# Battery_PSU.net
KiCad netlist of a schematic drawn in Altium Designer
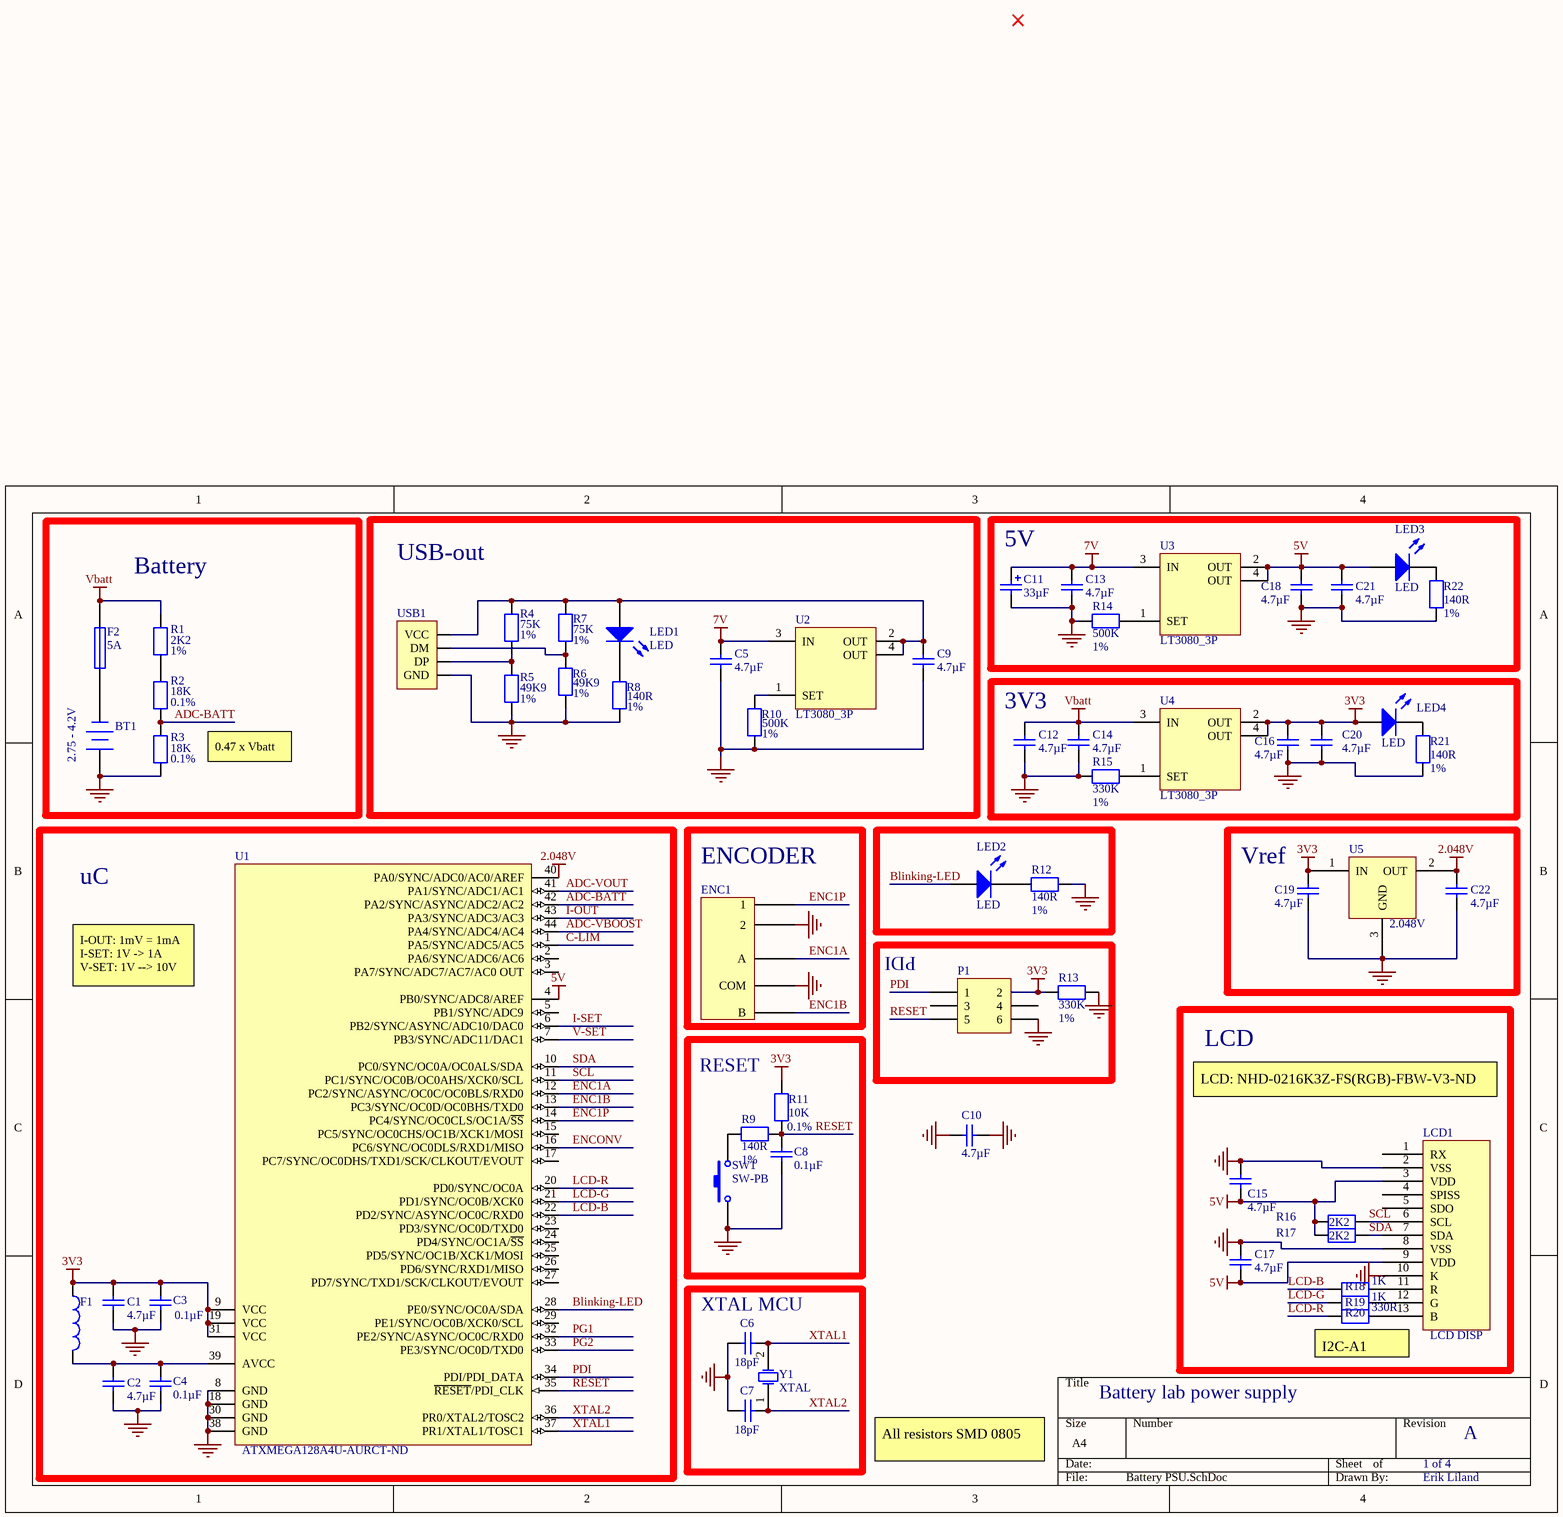
[diagram p0: Battery PSU.SchDoc]

(export (version "E")
  (design (tool "Eeschema 10.0.6"))
  (components
    (comp (ref "BT1")
      (value "2.75 - 4.2V")
      (footprint "BatteruPSU:Quad battery holder")
      (description "Multicell Battery")
      (fields
        (field (name "MANUFACTURER") "MPD (Memory Protection Devices)")
        (field (name "MANUFACTURER PART NUMBER") "BK-18650-PC8")
        (field (name "PUBLISHER") "Altium Limited")
      )
      (libsource (lib "BatteryPSU-parts") (part "Battery"))
    )
    (comp (ref "C1")
      (value "4.7µF")
      (footprint "BatteruPSU:0805_N_CAP")
      (description "Capacitor")
      (fields
        (field (name "MANUFACTURER") "Samsung Electro-Mechanics America, Inc")
        (field (name "MANUFACTURER PART NUMBER") "CL21B475KOFNFNE")
      )
      (libsource (lib "BatteryPSU-parts") (part "Cap"))
    )
    (comp (ref "C2")
      (value "4.7µF")
      (footprint "BatteruPSU:0805_N_CAP")
      (description "Capacitor")
      (fields
        (field (name "MANUFACTURER") "Samsung Electro-Mechanics America, Inc")
        (field (name "MANUFACTURER PART NUMBER") "CL21B475KOFNFNE")
      )
      (libsource (lib "BatteryPSU-parts") (part "Cap"))
    )
    (comp (ref "C3")
      (value "0.1µF")
      (footprint "BatteruPSU:0805_N_CAP")
      (description "Capacitor")
      (fields
        (field (name "MANUFACTURER") "Kemet")
        (field (name "MANUFACTURER PART NUMBER") "C0805C104K4RACTU")
      )
      (libsource (lib "BatteryPSU-parts") (part "Cap"))
    )
    (comp (ref "C4")
      (value "0.1µF")
      (footprint "BatteruPSU:0805_N_CAP")
      (description "Capacitor")
      (fields
        (field (name "MANUFACTURER") "Kemet")
        (field (name "MANUFACTURER PART NUMBER") "C0805C104K4RACTU")
      )
      (libsource (lib "BatteryPSU-parts") (part "Cap"))
    )
    (comp (ref "C5")
      (value "4.7µF")
      (footprint "BatteruPSU:0805_N_CAP")
      (description "Capacitor")
      (fields
        (field (name "MANUFACTURER") "Samsung Electro-Mechanics America, Inc")
        (field (name "MANUFACTURER PART NUMBER") "CL21B475KOFNFNE")
      )
      (libsource (lib "BatteryPSU-parts") (part "Cap"))
    )
    (comp (ref "C6")
      (value "18pF")
      (footprint "BatteruPSU:0805_N_CAP")
      (description "Capacitor")
      (fields
        (field (name "MANUFACTURER") "Samsung Electro-Mechanics America, Inc")
        (field (name "MANUFACTURER PART NUMBER") "CL21C180GBANNNC")
      )
      (libsource (lib "BatteryPSU-parts") (part "Cap"))
    )
    (comp (ref "C7")
      (value "18pF")
      (footprint "BatteruPSU:0805_N_CAP")
      (description "Capacitor")
      (fields
        (field (name "MANUFACTURER") "Samsung Electro-Mechanics America, Inc")
        (field (name "MANUFACTURER PART NUMBER") "CL21C180GBANNNC")
      )
      (libsource (lib "BatteryPSU-parts") (part "Cap"))
    )
    (comp (ref "C8")
      (value "0.1µF")
      (footprint "BatteruPSU:0805_N_CAP")
      (description "Capacitor")
      (fields
        (field (name "MANUFACTURER") "Kemet")
        (field (name "MANUFACTURER PART NUMBER") "C0805C104K4RACTU")
      )
      (libsource (lib "BatteryPSU-parts") (part "Cap"))
    )
    (comp (ref "C9")
      (value "4.7µF")
      (footprint "BatteruPSU:0805_N_CAP")
      (description "Capacitor")
      (fields
        (field (name "MANUFACTURER") "Samsung Electro-Mechanics America, Inc")
        (field (name "MANUFACTURER PART NUMBER") "CL21B475KOFNFNE")
      )
      (libsource (lib "BatteryPSU-parts") (part "Cap"))
    )
    (comp (ref "C10")
      (value "4.7µF")
      (footprint "BatteruPSU:0805_N_CAP")
      (description "Capacitor")
      (fields
        (field (name "MANUFACTURER") "Samsung Electro-Mechanics America, Inc")
        (field (name "MANUFACTURER PART NUMBER") "CL21B475KOFNFNE")
      )
      (libsource (lib "BatteryPSU-parts") (part "Cap"))
    )
    (comp (ref "C11")
      (value "33µF")
      (footprint "BatteruPSU:CAP SMD (F)")
      (description "Polarized Capacitor")
      (fields
        (field (name "MANUFACTURER") "Panasonic Electronic Components")
        (field (name "MANUFACTURER PART NUMBER") "EEH-ZA1E330R")
      )
      (libsource (lib "BatteryPSU-parts") (part "Cap Pol"))
    )
    (comp (ref "C12")
      (value "4.7µF")
      (footprint "BatteruPSU:0805_N_CAP")
      (description "Capacitor")
      (fields
        (field (name "MANUFACTURER") "Samsung Electro-Mechanics America, Inc")
        (field (name "MANUFACTURER PART NUMBER") "CL21B475KOFNFNE")
      )
      (libsource (lib "BatteryPSU-parts") (part "Cap"))
    )
    (comp (ref "C13")
      (value "4.7µF")
      (footprint "BatteruPSU:0805_N_CAP")
      (description "Capacitor")
      (fields
        (field (name "MANUFACTURER") "Samsung Electro-Mechanics America, Inc")
        (field (name "MANUFACTURER PART NUMBER") "CL21B475KOFNFNE")
      )
      (libsource (lib "BatteryPSU-parts") (part "Cap"))
    )
    (comp (ref "C14")
      (value "4.7µF")
      (footprint "BatteruPSU:0805_N_CAP")
      (description "Capacitor")
      (fields
        (field (name "MANUFACTURER") "Samsung Electro-Mechanics America, Inc")
        (field (name "MANUFACTURER PART NUMBER") "CL21B475KOFNFNE")
      )
      (libsource (lib "BatteryPSU-parts") (part "Cap"))
    )
    (comp (ref "C15")
      (value "4.7µF")
      (footprint "BatteruPSU:0805_N_CAP")
      (description "Capacitor")
      (fields
        (field (name "MANUFACTURER") "Samsung Electro-Mechanics America, Inc")
        (field (name "MANUFACTURER PART NUMBER") "CL21B475KOFNFNE")
      )
      (libsource (lib "BatteryPSU-parts") (part "Cap"))
    )
    (comp (ref "C16")
      (value "4.7µF")
      (footprint "BatteruPSU:0805_N_CAP")
      (description "Capacitor")
      (fields
        (field (name "MANUFACTURER") "Samsung Electro-Mechanics America, Inc")
        (field (name "MANUFACTURER PART NUMBER") "CL21B475KOFNFNE")
      )
      (libsource (lib "BatteryPSU-parts") (part "Cap"))
    )
    (comp (ref "C17")
      (value "4.7µF")
      (footprint "BatteruPSU:0805_N_CAP")
      (description "Capacitor")
      (fields
        (field (name "MANUFACTURER") "Samsung Electro-Mechanics America, Inc")
        (field (name "MANUFACTURER PART NUMBER") "CL21B475KOFNFNE")
      )
      (libsource (lib "BatteryPSU-parts") (part "Cap"))
    )
    (comp (ref "C18")
      (value "4.7µF")
      (footprint "BatteruPSU:0805_N_CAP")
      (description "Capacitor")
      (fields
        (field (name "MANUFACTURER") "Samsung Electro-Mechanics America, Inc")
        (field (name "MANUFACTURER PART NUMBER") "CL21B475KOFNFNE")
      )
      (libsource (lib "BatteryPSU-parts") (part "Cap"))
    )
    (comp (ref "C19")
      (value "4.7µF")
      (footprint "BatteruPSU:0805_N_CAP")
      (description "Capacitor")
      (fields
        (field (name "MANUFACTURER") "Samsung Electro-Mechanics America, Inc")
        (field (name "MANUFACTURER PART NUMBER") "CL21B475KOFNFNE")
      )
      (libsource (lib "BatteryPSU-parts") (part "Cap"))
    )
    (comp (ref "C20")
      (value "4.7µF")
      (footprint "BatteruPSU:0805_N_CAP")
      (description "Capacitor")
      (fields
        (field (name "MANUFACTURER") "Samsung Electro-Mechanics America, Inc")
        (field (name "MANUFACTURER PART NUMBER") "CL21B475KOFNFNE")
      )
      (libsource (lib "BatteryPSU-parts") (part "Cap"))
    )
    (comp (ref "C21")
      (value "4.7µF")
      (footprint "BatteruPSU:0805_N_CAP")
      (description "Capacitor")
      (fields
        (field (name "MANUFACTURER") "Samsung Electro-Mechanics America, Inc")
        (field (name "MANUFACTURER PART NUMBER") "CL21B475KOFNFNE")
      )
      (libsource (lib "BatteryPSU-parts") (part "Cap"))
    )
    (comp (ref "C22")
      (value "4.7µF")
      (footprint "BatteruPSU:0805_N_CAP")
      (description "Capacitor")
      (fields
        (field (name "MANUFACTURER") "Samsung Electro-Mechanics America, Inc")
        (field (name "MANUFACTURER PART NUMBER") "CL21B475KOFNFNE")
      )
      (libsource (lib "BatteryPSU-parts") (part "Cap"))
    )
    (comp (ref "ENC1")
      (value "RotEnc")
      (footprint "Bourns rotary encoder")
      (description "RotaryEncoder")
      (fields
        (field (name "MANUFACTURER") "Bourns Inc.")
        (field (name "MANUFACTURER PART NUMBER") "PEC09-2220F-S0012")
      )
      (libsource (lib "BatteryPSU-parts") (part "RotEnc"))
    )
    (comp (ref "F1")
      (value "200 Ohm @ 100MHz")
      (footprint "BatteruPSU:0805_N_FER")
      (description "Ferrite Bead")
      (fields
        (field (name "MANUFACTURER") "Laird-Signal Integrity Products")
        (field (name "MANUFACTURER PART NUMBER") "LI0805G201R-10")
      )
      (libsource (lib "BatteryPSU-parts") (part "Ferite"))
    )
    (comp (ref "F2")
      (value "5A")
      (footprint "BatteruPSU:1812_N_FUSE")
      (description "Resetable fuse, SMD")
      (fields
        (field (name "MANUFACTURER") "Bel Fuse Inc")
        (field (name "MANUFACTURER PART NUMBER") "0ZCG0260FF2C")
        (field (name "CURRENT - TRIP (IT)") "5A")
      )
      (libsource (lib "BatteryPSU-parts") (part "Fuse"))
    )
    (comp (ref "LCD1")
      (value "LCD DISP")
      (footprint "BatteruPSU:14P header")
      (description "2x16 CHAR DISP, RGB")
      (fields
        (field (name "MANUFACTURER") "Sullins Connector Solutions")
        (field (name "MANUFACTURER PART NUMBER") "SBH11-NBPC-D07-SM-BK")
      )
      (libsource (lib "BatteryPSU-parts") (part "LCD DISP"))
    )
    (comp (ref "LED1")
      (value "LED")
      (footprint "BatteruPSU:0805_N_LED")
      (description "Typical RED, GREEN, YELLOW, AMBER")
      (fields
        (field (name "MANUFACTURER") "OSRAM Opto Semiconductors Inc")
        (field (name "MANUFACTURER PART NUMBER") "LG R971-KN-1")
      )
      (libsource (lib "BatteryPSU-parts") (part "LED"))
    )
    (comp (ref "LED2")
      (value "LED")
      (footprint "BatteruPSU:0805_N_LED")
      (description "Typical RED, GREEN, YELLOW, AMBER")
      (fields
        (field (name "MANUFACTURER") "OSRAM Opto Semiconductors Inc")
        (field (name "MANUFACTURER PART NUMBER") "LG R971-KN-1")
      )
      (libsource (lib "BatteryPSU-parts") (part "LED"))
    )
    (comp (ref "LED3")
      (value "LED")
      (footprint "BatteruPSU:0805_N_LED")
      (description "Typical RED, GREEN, YELLOW, AMBER")
      (fields
        (field (name "MANUFACTURER") "OSRAM Opto Semiconductors Inc")
        (field (name "MANUFACTURER PART NUMBER") "LG R971-KN-1")
      )
      (libsource (lib "BatteryPSU-parts") (part "LED"))
    )
    (comp (ref "LED4")
      (value "LED")
      (footprint "BatteruPSU:0805_N_LED")
      (description "Typical RED, GREEN, YELLOW, AMBER")
      (fields
        (field (name "MANUFACTURER") "OSRAM Opto Semiconductors Inc")
        (field (name "MANUFACTURER PART NUMBER") "LG R971-KN-1")
      )
      (libsource (lib "BatteryPSU-parts") (part "LED"))
    )
    (comp (ref "P1")
      (value "Header 3X2")
      (footprint "BatteruPSU:HDR2X3 SMD")
      (description "Header, 3-Pin, Dual row")
      (fields (field (name "MANUFACTURER") "FCI") (field (name "MANUFACTURER PART NUMBER") "95278-101A06LF"))
      (libsource (lib "BatteryPSU-parts") (part "Header 3X2"))
    )
    (comp (ref "R1")
      (value "2K2")
      (footprint "BatteruPSU:0805_N_RES")
      (description "Resistor")
      (fields
        (field (name "TOLERANCE") "1%")
        (field (name "MANUFACTURER") "Samsung Electro-Mechanics America, Inc")
        (field (name "MANUFACTURER PART NUMBER") "RC2012F222CS")
      )
      (libsource (lib "BatteryPSU-parts") (part "Res"))
    )
    (comp (ref "R2")
      (value "18K")
      (footprint "BatteruPSU:0805_N_RES")
      (description "Resistor")
      (fields
        (field (name "TOLERANCE") "0.1%")
        (field (name "MANUFACTURER") "Panasonic Electronic Components")
        (field (name "MANUFACTURER PART NUMBER") "ERA-6AEB183V")
      )
      (libsource (lib "") (part "Res_1"))
    )
    (comp (ref "R3")
      (value "18K")
      (footprint "BatteruPSU:0805_N_RES")
      (description "Resistor")
      (fields
        (field (name "TOLERANCE") "0.1%")
        (field (name "MANUFACTURER") "Panasonic Electronic Components")
        (field (name "MANUFACTURER PART NUMBER") "ERA-6AEB183V")
      )
      (libsource (lib "") (part "Res_1"))
    )
    (comp (ref "R4")
      (value "75K")
      (footprint "BatteruPSU:0805_N_RES")
      (description "Resistor")
      (fields (field (name "TOLERANCE") "1%"))
      (libsource (lib "BatteryPSU-parts") (part "Res"))
    )
    (comp (ref "R5")
      (value "49K9")
      (footprint "BatteruPSU:0805_N_RES")
      (description "Resistor")
      (fields
        (field (name "TOLERANCE") "1%")
        (field (name "MANUFACTURER") "Samsung Electro-Mechanics America, Inc")
        (field (name "MANUFACTURER PART NUMBER") "RC2012F4992CS")
      )
      (libsource (lib "BatteryPSU-parts") (part "Res"))
    )
    (comp (ref "R6")
      (value "49K9")
      (footprint "BatteruPSU:0805_N_RES")
      (description "Resistor")
      (fields
        (field (name "TOLERANCE") "1%")
        (field (name "MANUFACTURER") "Samsung Electro-Mechanics America, Inc")
        (field (name "MANUFACTURER PART NUMBER") "RC2012F4992CS")
      )
      (libsource (lib "BatteryPSU-parts") (part "Res"))
    )
    (comp (ref "R7")
      (value "75K")
      (footprint "BatteruPSU:0805_N_RES")
      (description "Resistor")
      (fields (field (name "TOLERANCE") "1%"))
      (libsource (lib "BatteryPSU-parts") (part "Res"))
    )
    (comp (ref "R8")
      (value "140R")
      (footprint "BatteruPSU:0805_N_RES")
      (description "Resistor")
      (fields
        (field (name "TOLERANCE") "1%")
        (field (name "MANUFACTURER") "Samsung Electro-Mechanics America, Inc")
        (field (name "MANUFACTURER PART NUMBER") "RC2012F1400CS")
      )
      (libsource (lib "BatteryPSU-parts") (part "Res"))
    )
    (comp (ref "R9")
      (value "140R")
      (footprint "BatteruPSU:0805_N_RES")
      (description "Resistor")
      (fields
        (field (name "TOLERANCE") "1%")
        (field (name "MANUFACTURER") "Samsung Electro-Mechanics America, Inc")
        (field (name "MANUFACTURER PART NUMBER") "RC2012F1400CS")
      )
      (libsource (lib "") (part "Res_3"))
    )
    (comp (ref "R10")
      (value "500K")
      (footprint "BatteruPSU:0805_N_RES")
      (description "Resistor")
      (fields (field (name "TOLERANCE") "1%"))
      (libsource (lib "BatteryPSU-parts") (part "Res"))
    )
    (comp (ref "R11")
      (value "10K")
      (footprint "BatteruPSU:0805_N_RES")
      (description "Resistor")
      (fields
        (field (name "TOLERANCE") "0.1%")
        (field (name "MANUFACTURER") "TE Connectivity AMP Connectors")
        (field (name "MANUFACTURER PART NUMBER") "8-1614884-4")
      )
      (libsource (lib "") (part "Res_1"))
    )
    (comp (ref "R12")
      (value "140R")
      (footprint "BatteruPSU:0805_N_RES")
      (description "Resistor")
      (fields
        (field (name "TOLERANCE") "1%")
        (field (name "MANUFACTURER") "Samsung Electro-Mechanics America, Inc")
        (field (name "MANUFACTURER PART NUMBER") "RC2012F1400CS")
      )
      (libsource (lib "") (part "Res_2"))
    )
    (comp (ref "R13")
      (value "330K")
      (footprint "BatteruPSU:0805_N_RES")
      (description "Resistor")
      (fields
        (field (name "TOLERANCE") "1%")
        (field (name "MANUFACTURER") "Samsung Electro-Mechanics America, Inc")
        (field (name "MANUFACTURER PART NUMBER") "RC2012F331CS")
      )
      (libsource (lib "") (part "Res_2"))
    )
    (comp (ref "R14")
      (value "500K")
      (footprint "BatteruPSU:0805_N_RES")
      (description "Resistor")
      (fields (field (name "TOLERANCE") "1%"))
      (libsource (lib "") (part "Res_2"))
    )
    (comp (ref "R15")
      (value "330K")
      (footprint "BatteruPSU:0805_N_RES")
      (description "Resistor")
      (fields
        (field (name "TOLERANCE") "1%")
        (field (name "MANUFACTURER") "Samsung Electro-Mechanics America, Inc")
        (field (name "MANUFACTURER PART NUMBER") "RC2012F331CS")
      )
      (libsource (lib "") (part "Res_2"))
    )
    (comp (ref "R16")
      (value "2K2")
      (footprint "BatteruPSU:0805_N_RES")
      (description "Resistor")
      (fields
        (field (name "TOLERANCE") "1%")
        (field (name "MANUFACTURER") "Samsung Electro-Mechanics America, Inc")
      )
      (libsource (lib "") (part "Res_2"))
    )
    (comp (ref "R17")
      (value "2K2")
      (footprint "BatteruPSU:0805_N_RES")
      (description "Resistor")
      (fields
        (field (name "TOLERANCE") "1%")
        (field (name "MANUFACTURER") "Samsung Electro-Mechanics America, Inc")
      )
      (libsource (lib "") (part "Res_2"))
    )
    (comp (ref "R18")
      (value "1K")
      (footprint "BatteruPSU:0805_N_RES")
      (description "Resistor")
      (fields
        (field (name "TOLERANCE") "0.1%")
        (field (name "MANUFACTURER") "Panasonic Electronic Components")
      )
      (libsource (lib "") (part "Res_2"))
    )
    (comp (ref "R19")
      (value "1K")
      (footprint "BatteruPSU:0805_N_RES")
      (description "Resistor")
      (fields
        (field (name "TOLERANCE") "0.1%")
        (field (name "MANUFACTURER") "Panasonic Electronic Components")
      )
      (libsource (lib "") (part "Res_2"))
    )
    (comp (ref "R20")
      (value "330R")
      (footprint "BatteruPSU:0805_N_RES")
      (description "Resistor")
      (fields
        (field (name "TOLERANCE") "1%")
        (field (name "MANUFACTURER") "Samsung Electro-Mechanics America, Inc")
      )
      (libsource (lib "") (part "Res_2"))
    )
    (comp (ref "R21")
      (value "140R")
      (footprint "BatteruPSU:0805_N_RES")
      (description "Resistor")
      (fields
        (field (name "TOLERANCE") "1%")
        (field (name "MANUFACTURER") "Samsung Electro-Mechanics America, Inc")
        (field (name "MANUFACTURER PART NUMBER") "RC2012F1400CS")
      )
      (libsource (lib "") (part "Res_1"))
    )
    (comp (ref "R22")
      (value "140R")
      (footprint "BatteruPSU:0805_N_RES")
      (description "Resistor")
      (fields
        (field (name "TOLERANCE") "1%")
        (field (name "MANUFACTURER") "Samsung Electro-Mechanics America, Inc")
        (field (name "MANUFACTURER PART NUMBER") "RC2012F1400CS")
      )
      (libsource (lib "") (part "Res_1"))
    )
    (comp (ref "SW1")
      (value "SW-PB")
      (footprint "BatteruPSU:SW TACTILE")
      (description "Switch")
      (fields
        (field (name "MANUFACTURER") "C&K Components")
        (field (name "MANUFACTURER PART NUMBER") "PTS645SK50SMTR92 LFS")
        (field (name "PUBLISHER") "Altium Limited")
      )
      (libsource (lib "BatteryPSU-parts") (part "SW-PB"))
    )
    (comp (ref "U1")
      (value "ATxmega128A4-AU")
      (footprint "44A_N")
      (fields
        (field (name "SUPPLIER PART NUMBER 1") "ATXMEGA128A4U-AURCT-ND")
        (field (name "MANUFACTURER") "Atmel")
        (field (name "MANUFACTURER PART NUMBER") "ATXMEGA128A4U-AUR")
      )
      (libsource (lib "Altium Content Vault") (part "CMP-0094-00040-4"))
    )
    (comp (ref "U2")
      (value "LT3080_3P")
      (footprint "BatteruPSU:SOT223_N")
      (description "LT3080 LDO regulator")
      (fields
        (field (name "MANUFACTURER") "Linear Technology")
        (field (name "MANUFACTURER PART NUMBER") "LT3080EST#TRPBF")
      )
      (libsource (lib "BatteryPSU-parts") (part "LT3080_3P"))
    )
    (comp (ref "U3")
      (value "LT3080_3P")
      (footprint "BatteruPSU:SOT223_N")
      (description "LT3080 LDO regulator")
      (fields
        (field (name "MANUFACTURER") "Linear Technology")
        (field (name "MANUFACTURER PART NUMBER") "LT3080EST#TRPBF")
      )
      (libsource (lib "BatteryPSU-parts") (part "LT3080_3P"))
    )
    (comp (ref "U4")
      (value "LT3080_3P")
      (footprint "BatteruPSU:SOT223_N")
      (description "LT3080 LDO regulator")
      (fields
        (field (name "MANUFACTURER") "Linear Technology")
        (field (name "MANUFACTURER PART NUMBER") "LT3080EST#TRPBF")
      )
      (libsource (lib "BatteryPSU-parts") (part "LT3080_3P"))
    )
    (comp (ref "U5")
      (value "2.048V")
      (footprint "BatteruPSU:SOT-23_N")
      (description "Voltage reference")
      (fields
        (field (name "MANUFACTURER") "Intersil")
        (field (name "MANUFACTURER PART NUMBER") "ISL21010CFH320Z-TK")
      )
      (libsource (lib "BatteryPSU-parts") (part "ISL21010"))
    )
    (comp (ref "USB1")
      (value "USB_A_VERT")
      (footprint "BatteruPSU:USB A VERT")
      (description "USB A Vertikal")
      (fields
        (field (name "MANUFACTURER") "Assmann WSW Components")
        (field (name "MANUFACTURER PART NUMBER") "A-USB/2-A-E-R")
      )
      (libsource (lib "BatteryPSU-parts") (part "USB_A_VERT"))
    )
    (comp (ref "Y1")
      (value "XTAL")
      (footprint "BatteruPSU:XTAL SMD")
      (description "Crystal Oscillator")
      (fields
        (field (name "MANUFACTURER") "ECS Inc")
        (field (name "MANUFACTURER PART NUMBER") "ECS-80-18-20BQ-DS")
        (field (name "PUBLISHER") "Altium Limited")
      )
      (libsource (lib "BatteryPSU-parts") (part "XTAL"))
    )
  )
  (nets
    (net (code "1") (name "/ADC-BATT") (class "Default")
      (node (ref "R2") (pin "2") (pinfunction "2_2") (pintype "passive"))
      (node (ref "R3") (pin "1") (pinfunction "1_1") (pintype "passive"))
      (node (ref "U1") (pin "42") (pinfunction "PA2/SYNC/ASYNC/ADC2/AC2_42") (pintype "bidirectional"))
    )
    (net (code "2") (name "/ADC-VBOOST") (class "Default")
      (node (ref "U1") (pin "44") (pinfunction "PA4/SYNC/ADC4/AC4_44") (pintype "bidirectional"))
    )
    (net (code "3") (name "/ADC-VOUT") (class "Default")
      (node (ref "U1") (pin "41") (pinfunction "PA1/SYNC/ADC1/AC1_41") (pintype "bidirectional"))
    )
    (net (code "4") (name "/Blinking-LED") (class "Default")
      (node (ref "LED2") (pin "1") (pinfunction "A_1") (pintype "passive"))
      (node (ref "U1") (pin "28") (pinfunction "PE0/SYNC/OC0A/SDA_28") (pintype "bidirectional"))
    )
    (net (code "5") (name "/C-LIM") (class "Default")
      (node (ref "U1") (pin "1") (pinfunction "PA5/SYNC/ADC5/AC5_1") (pintype "bidirectional"))
    )
    (net (code "6") (name "/ENC1A") (class "Default")
      (node (ref "ENC1") (pin "A") (pinfunction "A_A") (pintype "passive"))
      (node (ref "U1") (pin "12") (pinfunction "PC2/SYNC/ASYNC/OC0C/OC0BLS/RXD0_12") (pintype "bidirectional"))
    )
    (net (code "7") (name "/ENC1B") (class "Default")
      (node (ref "ENC1") (pin "B") (pinfunction "B_B") (pintype "passive"))
      (node (ref "U1") (pin "13") (pinfunction "PC3/SYNC/OC0D/OC0BHS/TXD0_13") (pintype "bidirectional"))
    )
    (net (code "8") (name "/ENC1P") (class "Default")
      (node (ref "ENC1") (pin "D") (pinfunction "1_D") (pintype "passive"))
      (node (ref "U1") (pin "14") (pinfunction "PC4/SYNC/OC0CLS/OC1A/~{SS}_14") (pintype "bidirectional"))
    )
    (net (code "9") (name "/ENCONV") (class "Default")
      (node (ref "U1") (pin "16") (pinfunction "PC6/SYNC/OC0DLS/RXD1/MISO_16") (pintype "bidirectional"))
    )
    (net (code "10") (name "/I-OUT") (class "Default")
      (node (ref "U1") (pin "43") (pinfunction "PA3/SYNC/ADC3/AC3_43") (pintype "bidirectional"))
    )
    (net (code "11") (name "/I-SET") (class "Default")
      (node (ref "U1") (pin "6") (pinfunction "PB2/SYNC/ASYNC/ADC10/DAC0_6") (pintype "bidirectional"))
    )
    (net (code "12") (name "/LCD-B") (class "Default")
      (node (ref "R18") (pin "2") (pinfunction "2_2") (pintype "passive"))
      (node (ref "U1") (pin "22") (pinfunction "PD2/SYNC/ASYNC/OC0C/RXD0_22") (pintype "bidirectional"))
    )
    (net (code "13") (name "/LCD-G") (class "Default")
      (node (ref "R19") (pin "2") (pinfunction "2_2") (pintype "passive"))
      (node (ref "U1") (pin "21") (pinfunction "PD1/SYNC/OC0B/XCK0_21") (pintype "bidirectional"))
    )
    (net (code "14") (name "/LCD-R") (class "Default")
      (node (ref "R20") (pin "2") (pinfunction "2_2") (pintype "passive"))
      (node (ref "U1") (pin "20") (pinfunction "PD0/SYNC/OC0A_20") (pintype "bidirectional"))
    )
    (net (code "15") (name "/PDI") (class "Default")
      (node (ref "P1") (pin "1") (pinfunction "1_1") (pintype "passive"))
      (node (ref "U1") (pin "34") (pinfunction "PDI/PDI_DATA_34") (pintype "bidirectional"))
    )
    (net (code "16") (name "/PG1") (class "Default")
      (node (ref "U1") (pin "32") (pinfunction "PE2/SYNC/ASYNC/OC0C/RXD0_32") (pintype "bidirectional"))
    )
    (net (code "17") (name "/PG2") (class "Default")
      (node (ref "U1") (pin "33") (pinfunction "PE3/SYNC/OC0D/TXD0_33") (pintype "bidirectional"))
    )
    (net (code "18") (name "/RESET") (class "Default")
      (node (ref "C8") (pin "2") (pinfunction "2_2") (pintype "passive"))
      (node (ref "P1") (pin "5") (pinfunction "5_5") (pintype "passive"))
      (node (ref "R11") (pin "2") (pinfunction "2_2") (pintype "passive"))
      (node (ref "R9") (pin "2") (pinfunction "2_2") (pintype "passive"))
      (node (ref "U1") (pin "35") (pinfunction "~{RESET}/PDI_CLK_35") (pintype "input"))
    )
    (net (code "19") (name "/SCL") (class "Default")
      (node (ref "LCD1") (pin "6") (pinfunction "SCL_6") (pintype "passive"))
      (node (ref "R16") (pin "1") (pinfunction "1_1") (pintype "passive"))
      (node (ref "U1") (pin "11") (pinfunction "PC1/SYNC/OC0B/OC0AHS/XCK0/SCL_11") (pintype "bidirectional"))
    )
    (net (code "20") (name "/SDA") (class "Default")
      (node (ref "LCD1") (pin "7") (pinfunction "SDA_7") (pintype "passive"))
      (node (ref "R17") (pin "1") (pinfunction "1_1") (pintype "passive"))
      (node (ref "U1") (pin "10") (pinfunction "PC0/SYNC/OC0A/OC0ALS/SDA_10") (pintype "bidirectional"))
    )
    (net (code "21") (name "/V-SET") (class "Default")
      (node (ref "U1") (pin "7") (pinfunction "PB3/SYNC/ADC11/DAC1_7") (pintype "bidirectional"))
    )
    (net (code "22") (name "/XTAL1") (class "Default")
      (node (ref "C6") (pin "2") (pinfunction "2_2") (pintype "passive"))
      (node (ref "U1") (pin "37") (pinfunction "PR1/XTAL1/TOSC1_37") (pintype "bidirectional"))
      (node (ref "Y1") (pin "2") (pinfunction "OSC2_2") (pintype "passive"))
    )
    (net (code "23") (name "/XTAL2") (class "Default")
      (node (ref "C7") (pin "2") (pinfunction "2_2") (pintype "passive"))
      (node (ref "U1") (pin "36") (pinfunction "PR0/XTAL2/TOSC2_36") (pintype "bidirectional"))
      (node (ref "Y1") (pin "1") (pinfunction "OSC1_1") (pintype "passive"))
    )
    (net (code "24") (name "2.048V") (class "Default")
      (node (ref "C22") (pin "1") (pinfunction "1_1") (pintype "passive"))
      (node (ref "U1") (pin "40") (pinfunction "PA0/SYNC/ADC0/AC0/AREF_40") (pintype "passive"))
      (node (ref "U5") (pin "2") (pinfunction "OUT_2") (pintype "passive"))
    )
    (net (code "25") (name "3V3") (class "Default")
      (node (ref "C1") (pin "1") (pinfunction "1_1") (pintype "passive"))
      (node (ref "C16") (pin "1") (pinfunction "1_1") (pintype "passive"))
      (node (ref "C19") (pin "1") (pinfunction "1_1") (pintype "passive"))
      (node (ref "C20") (pin "1") (pinfunction "1_1") (pintype "passive"))
      (node (ref "C3") (pin "2") (pinfunction "2_2") (pintype "passive"))
      (node (ref "F1") (pin "1") (pinfunction "1_1") (pintype "passive"))
      (node (ref "LED4") (pin "1") (pinfunction "A_1") (pintype "passive"))
      (node (ref "P1") (pin "2") (pinfunction "2_2") (pintype "passive"))
      (node (ref "R11") (pin "1") (pinfunction "1_1") (pintype "passive"))
      (node (ref "R13") (pin "2") (pinfunction "2_2") (pintype "passive"))
      (node (ref "U1") (pin "19") (pinfunction "VCC_19") (pintype "power_in"))
      (node (ref "U1") (pin "31") (pinfunction "VCC_31") (pintype "power_in"))
      (node (ref "U1") (pin "9") (pinfunction "VCC_9") (pintype "power_in"))
      (node (ref "U4") (pin "2") (pinfunction "OUT_2") (pintype "passive"))
      (node (ref "U4") (pin "4") (pinfunction "OUT_4") (pintype "passive"))
      (node (ref "U5") (pin "1") (pinfunction "IN_1") (pintype "passive"))
    )
    (net (code "26") (name "5V") (class "Default")
      (node (ref "C15") (pin "2") (pinfunction "2_2") (pintype "passive"))
      (node (ref "C17") (pin "2") (pinfunction "2_2") (pintype "passive"))
      (node (ref "C18") (pin "1") (pinfunction "1_1") (pintype "passive"))
      (node (ref "C21") (pin "1") (pinfunction "1_1") (pintype "passive"))
      (node (ref "LCD1") (pin "3") (pinfunction "VDD_3") (pintype "passive"))
      (node (ref "LCD1") (pin "9") (pinfunction "VDD_9") (pintype "passive"))
      (node (ref "LED3") (pin "1") (pinfunction "A_1") (pintype "passive"))
      (node (ref "R16") (pin "2") (pinfunction "2_2") (pintype "passive"))
      (node (ref "R17") (pin "2") (pinfunction "2_2") (pintype "passive"))
      (node (ref "U1") (pin "4") (pinfunction "PB0/SYNC/ADC8/AREF_4") (pintype "passive"))
      (node (ref "U3") (pin "2") (pinfunction "OUT_2") (pintype "passive"))
      (node (ref "U3") (pin "4") (pinfunction "OUT_4") (pintype "passive"))
    )
    (net (code "27") (name "7V") (class "Default")
      (node (ref "C11") (pin "1") (pinfunction "1_1") (pintype "passive"))
      (node (ref "C13") (pin "1") (pinfunction "1_1") (pintype "passive"))
      (node (ref "C5") (pin "1") (pinfunction "1_1") (pintype "passive"))
      (node (ref "U2") (pin "3") (pinfunction "IN_3") (pintype "passive"))
      (node (ref "U3") (pin "3") (pinfunction "IN_3") (pintype "passive"))
    )
    (net (code "28") (name "GND") (class "Default")
      (node (ref "BT1") (pin "1") (pinfunction "+_1") (pintype "passive"))
      (node (ref "C1") (pin "2") (pinfunction "2_2") (pintype "passive"))
      (node (ref "C10") (pin "1") (pinfunction "1_1") (pintype "passive"))
      (node (ref "C10") (pin "2") (pinfunction "2_2") (pintype "passive"))
      (node (ref "C11") (pin "2") (pinfunction "2_2") (pintype "passive"))
      (node (ref "C12") (pin "2") (pinfunction "2_2") (pintype "passive"))
      (node (ref "C13") (pin "2") (pinfunction "2_2") (pintype "passive"))
      (node (ref "C14") (pin "2") (pinfunction "2_2") (pintype "passive"))
      (node (ref "C15") (pin "1") (pinfunction "1_1") (pintype "passive"))
      (node (ref "C16") (pin "2") (pinfunction "2_2") (pintype "passive"))
      (node (ref "C17") (pin "1") (pinfunction "1_1") (pintype "passive"))
      (node (ref "C18") (pin "2") (pinfunction "2_2") (pintype "passive"))
      (node (ref "C19") (pin "2") (pinfunction "2_2") (pintype "passive"))
      (node (ref "C2") (pin "2") (pinfunction "2_2") (pintype "passive"))
      (node (ref "C20") (pin "2") (pinfunction "2_2") (pintype "passive"))
      (node (ref "C21") (pin "2") (pinfunction "2_2") (pintype "passive"))
      (node (ref "C22") (pin "2") (pinfunction "2_2") (pintype "passive"))
      (node (ref "C3") (pin "1") (pinfunction "1_1") (pintype "passive"))
      (node (ref "C4") (pin "1") (pinfunction "1_1") (pintype "passive"))
      (node (ref "C5") (pin "2") (pinfunction "2_2") (pintype "passive"))
      (node (ref "C6") (pin "1") (pinfunction "1_1") (pintype "passive"))
      (node (ref "C7") (pin "1") (pinfunction "1_1") (pintype "passive"))
      (node (ref "C8") (pin "1") (pinfunction "1_1") (pintype "passive"))
      (node (ref "C9") (pin "2") (pinfunction "2_2") (pintype "passive"))
      (node (ref "ENC1") (pin "C") (pinfunction "COM_C") (pintype "passive"))
      (node (ref "ENC1") (pin "E") (pinfunction "2_E") (pintype "passive"))
      (node (ref "LCD1") (pin "10") (pinfunction "K_10") (pintype "passive"))
      (node (ref "LCD1") (pin "2") (pinfunction "VSS_2") (pintype "passive"))
      (node (ref "LCD1") (pin "8") (pinfunction "VSS_8") (pintype "passive"))
      (node (ref "P1") (pin "6") (pinfunction "6_6") (pintype "passive"))
      (node (ref "R10") (pin "1") (pinfunction "1_1") (pintype "passive"))
      (node (ref "R12") (pin "1") (pinfunction "1_1") (pintype "passive"))
      (node (ref "R13") (pin "1") (pinfunction "1_1") (pintype "passive"))
      (node (ref "R14") (pin "2") (pinfunction "2_2") (pintype "passive"))
      (node (ref "R15") (pin "2") (pinfunction "2_2") (pintype "passive"))
      (node (ref "R21") (pin "2") (pinfunction "2_2") (pintype "passive"))
      (node (ref "R22") (pin "2") (pinfunction "2_2") (pintype "passive"))
      (node (ref "R3") (pin "2") (pinfunction "2_2") (pintype "passive"))
      (node (ref "R5") (pin "1") (pinfunction "1_1") (pintype "passive"))
      (node (ref "R6") (pin "1") (pinfunction "1_1") (pintype "passive"))
      (node (ref "R8") (pin "1") (pinfunction "1_1") (pintype "passive"))
      (node (ref "SW1") (pin "1") (pinfunction "1_1") (pintype "passive"))
      (node (ref "U1") (pin "18") (pinfunction "GND_18") (pintype "power_in"))
      (node (ref "U1") (pin "30") (pinfunction "GND_30") (pintype "power_in"))
      (node (ref "U1") (pin "38") (pinfunction "GND_38") (pintype "power_in"))
      (node (ref "U1") (pin "8") (pinfunction "GND_8") (pintype "power_in"))
      (node (ref "U5") (pin "3") (pinfunction "GND_3") (pintype "passive"))
      (node (ref "USB1") (pin "4") (pinfunction "GND_4") (pintype "passive"))
    )
    (net (code "29") (name "Net-(BT1--)") (class "Default")
      (node (ref "BT1") (pin "2") (pinfunction "-_2") (pintype "passive"))
      (node (ref "F2") (pin "2") (pinfunction "2_2") (pintype "passive"))
    )
    (net (code "30") (name "Net-(LCD1-B)") (class "Default")
      (node (ref "LCD1") (pin "13") (pinfunction "B_13") (pintype "passive"))
      (node (ref "R20") (pin "1") (pinfunction "1_1") (pintype "passive"))
    )
    (net (code "31") (name "Net-(LCD1-G)") (class "Default")
      (node (ref "LCD1") (pin "12") (pinfunction "G_12") (pintype "passive"))
      (node (ref "R19") (pin "1") (pinfunction "1_1") (pintype "passive"))
    )
    (net (code "32") (name "Net-(LCD1-R)") (class "Default")
      (node (ref "LCD1") (pin "11") (pinfunction "R_11") (pintype "passive"))
      (node (ref "R18") (pin "1") (pinfunction "1_1") (pintype "passive"))
    )
    (net (code "33") (name "Net-(LED1-A)") (class "Default")
      (node (ref "C9") (pin "1") (pinfunction "1_1") (pintype "passive"))
      (node (ref "LED1") (pin "1") (pinfunction "A_1") (pintype "passive"))
      (node (ref "R4") (pin "2") (pinfunction "2_2") (pintype "passive"))
      (node (ref "R7") (pin "2") (pinfunction "2_2") (pintype "passive"))
      (node (ref "U2") (pin "2") (pinfunction "OUT_2") (pintype "passive"))
      (node (ref "U2") (pin "4") (pinfunction "OUT_4") (pintype "passive"))
      (node (ref "USB1") (pin "1") (pinfunction "VCC_1") (pintype "passive"))
    )
    (net (code "34") (name "Net-(LED1-K)") (class "Default")
      (node (ref "LED1") (pin "2") (pinfunction "K_2") (pintype "passive"))
      (node (ref "R8") (pin "2") (pinfunction "2_2") (pintype "passive"))
    )
    (net (code "35") (name "Net-(LED2-K)") (class "Default")
      (node (ref "LED2") (pin "2") (pinfunction "K_2") (pintype "passive"))
      (node (ref "R12") (pin "2") (pinfunction "2_2") (pintype "passive"))
    )
    (net (code "36") (name "Net-(LED3-K)") (class "Default")
      (node (ref "LED3") (pin "2") (pinfunction "K_2") (pintype "passive"))
      (node (ref "R22") (pin "1") (pinfunction "1_1") (pintype "passive"))
    )
    (net (code "37") (name "Net-(LED4-K)") (class "Default")
      (node (ref "LED4") (pin "2") (pinfunction "K_2") (pintype "passive"))
      (node (ref "R21") (pin "1") (pinfunction "1_1") (pintype "passive"))
    )
    (net (code "38") (name "Net-(R1-Pad1)") (class "Default")
      (node (ref "R1") (pin "1") (pinfunction "1_1") (pintype "passive"))
      (node (ref "R2") (pin "1") (pinfunction "1_1") (pintype "passive"))
    )
    (net (code "39") (name "Net-(R9-Pad1)") (class "Default")
      (node (ref "R9") (pin "1") (pinfunction "1_1") (pintype "passive"))
      (node (ref "SW1") (pin "2") (pinfunction "2_2") (pintype "passive"))
    )
    (net (code "40") (name "Net-(U1-AVCC)") (class "Default")
      (node (ref "C2") (pin "1") (pinfunction "1_1") (pintype "passive"))
      (node (ref "C4") (pin "2") (pinfunction "2_2") (pintype "passive"))
      (node (ref "F1") (pin "2") (pinfunction "2_2") (pintype "passive"))
      (node (ref "U1") (pin "39") (pinfunction "AVCC_39") (pintype "power_in"))
    )
    (net (code "41") (name "Net-(U2-SET)") (class "Default")
      (node (ref "R10") (pin "2") (pinfunction "2_2") (pintype "passive"))
      (node (ref "U2") (pin "1") (pinfunction "SET_1") (pintype "passive"))
    )
    (net (code "42") (name "Net-(U3-SET)") (class "Default")
      (node (ref "R14") (pin "1") (pinfunction "1_1") (pintype "passive"))
      (node (ref "U3") (pin "1") (pinfunction "SET_1") (pintype "passive"))
    )
    (net (code "43") (name "Net-(U4-SET)") (class "Default")
      (node (ref "R15") (pin "1") (pinfunction "1_1") (pintype "passive"))
      (node (ref "U4") (pin "1") (pinfunction "SET_1") (pintype "passive"))
    )
    (net (code "44") (name "Net-(USB1-DM)") (class "Default")
      (node (ref "R6") (pin "2") (pinfunction "2_2") (pintype "passive"))
      (node (ref "R7") (pin "1") (pinfunction "1_1") (pintype "passive"))
      (node (ref "USB1") (pin "2") (pinfunction "DM_2") (pintype "passive"))
    )
    (net (code "45") (name "Net-(USB1-DP)") (class "Default")
      (node (ref "R4") (pin "1") (pinfunction "1_1") (pintype "passive"))
      (node (ref "R5") (pin "2") (pinfunction "2_2") (pintype "passive"))
      (node (ref "USB1") (pin "3") (pinfunction "DP_3") (pintype "passive"))
    )
    (net (code "46") (name "Vbatt") (class "Default")
      (node (ref "C12") (pin "1") (pinfunction "1_1") (pintype "passive"))
      (node (ref "C14") (pin "1") (pinfunction "1_1") (pintype "passive"))
      (node (ref "F2") (pin "1") (pinfunction "1_1") (pintype "passive"))
      (node (ref "R1") (pin "2") (pinfunction "2_2") (pintype "passive"))
      (node (ref "U4") (pin "3") (pinfunction "IN_3") (pintype "passive"))
    )
    (net (code "47") (name "unconnected-(LCD1-RX-Pad1)") (class "Default")
      (node (ref "LCD1") (pin "1") (pinfunction "RX_1") (pintype "passive"))
    )
    (net (code "48") (name "unconnected-(LCD1-SDO-Pad5)") (class "Default")
      (node (ref "LCD1") (pin "5") (pinfunction "SDO_5") (pintype "passive"))
    )
    (net (code "49") (name "unconnected-(LCD1-SPISS-Pad4)") (class "Default")
      (node (ref "LCD1") (pin "4") (pinfunction "SPISS_4") (pintype "passive"))
    )
    (net (code "50") (name "unconnected-(P1-Pad3)") (class "Default")
      (node (ref "P1") (pin "3") (pinfunction "3_3") (pintype "passive"))
    )
    (net (code "51") (name "unconnected-(P1-Pad4)") (class "Default")
      (node (ref "P1") (pin "4") (pinfunction "4_4") (pintype "passive"))
    )
    (net (code "52") (name "unconnected-(U1-PA6{slash}SYNC{slash}ADC6{slash}AC6-Pad2)") (class "Default")
      (node (ref "U1") (pin "2") (pinfunction "PA6/SYNC/ADC6/AC6_2") (pintype "bidirectional"))
    )
    (net (code "53") (name "unconnected-(U1-PA7{slash}SYNC{slash}ADC7{slash}AC7{slash}AC0_OUT-Pad3)") (class "Default")
      (node (ref "U1") (pin "3") (pinfunction "PA7/SYNC/ADC7/AC7/AC0_OUT_3") (pintype "bidirectional"))
    )
    (net (code "54") (name "unconnected-(U1-PB1{slash}SYNC{slash}ADC9-Pad5)") (class "Default")
      (node (ref "U1") (pin "5") (pinfunction "PB1/SYNC/ADC9_5") (pintype "bidirectional"))
    )
    (net (code "55") (name "unconnected-(U1-PC5{slash}SYNC{slash}OC0CHS{slash}OC1B{slash}XCK1{slash}MOSI-Pad15)") (class "Default")
      (node (ref "U1") (pin "15") (pinfunction "PC5/SYNC/OC0CHS/OC1B/XCK1/MOSI_15") (pintype "bidirectional"))
    )
    (net (code "56") (name "unconnected-(U1-PC7{slash}SYNC{slash}OC0DHS{slash}TXD1{slash}SCK{slash}CLKOUT{slash}EVOUT-Pad17)") (class "Default")
      (node (ref "U1") (pin "17") (pinfunction "PC7/SYNC/OC0DHS/TXD1/SCK/CLKOUT/EVOUT_17") (pintype "bidirectional"))
    )
    (net (code "57") (name "unconnected-(U1-PD3{slash}SYNC{slash}OC0D{slash}TXD0-Pad23)") (class "Default")
      (node (ref "U1") (pin "23") (pinfunction "PD3/SYNC/OC0D/TXD0_23") (pintype "bidirectional"))
    )
    (net (code "58") (name "unconnected-(U1-PD4{slash}SYNC{slash}OC1A{slash}~{SS}-Pad24)") (class "Default")
      (node (ref "U1") (pin "24") (pinfunction "PD4/SYNC/OC1A/~{SS}_24") (pintype "bidirectional"))
    )
    (net (code "59") (name "unconnected-(U1-PD5{slash}SYNC{slash}OC1B{slash}XCK1{slash}MOSI-Pad25)") (class "Default")
      (node (ref "U1") (pin "25") (pinfunction "PD5/SYNC/OC1B/XCK1/MOSI_25") (pintype "bidirectional"))
    )
    (net (code "60") (name "unconnected-(U1-PD6{slash}SYNC{slash}RXD1{slash}MISO-Pad26)") (class "Default")
      (node (ref "U1") (pin "26") (pinfunction "PD6/SYNC/RXD1/MISO_26") (pintype "bidirectional"))
    )
    (net (code "61") (name "unconnected-(U1-PD7{slash}SYNC{slash}TXD1{slash}SCK{slash}CLKOUT{slash}EVOUT-Pad27)") (class "Default")
      (node (ref "U1") (pin "27") (pinfunction "PD7/SYNC/TXD1/SCK/CLKOUT/EVOUT_27") (pintype "bidirectional"))
    )
    (net (code "62") (name "unconnected-(U1-PE1{slash}SYNC{slash}OC0B{slash}XCK0{slash}SCL-Pad29)") (class "Default")
      (node (ref "U1") (pin "29") (pinfunction "PE1/SYNC/OC0B/XCK0/SCL_29") (pintype "bidirectional"))
    )
  )
)
